# v2164_quad_VC_mixer_0402.net
KiCad netlist of a schematic drawn in EAGLE
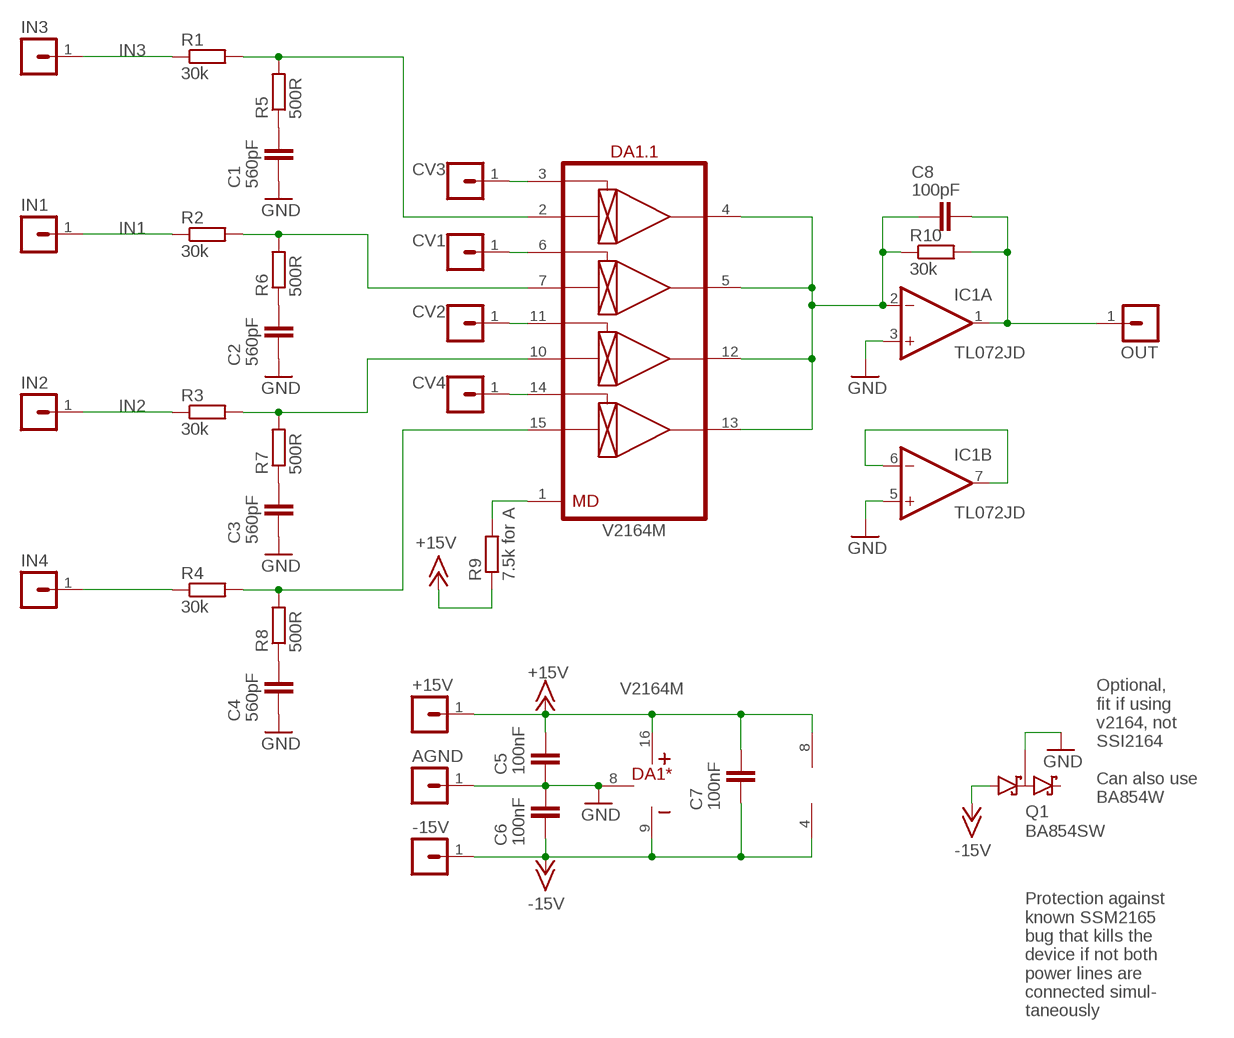
[diagram p0: schematic, sheet 1]

(export (version "E")
  (design (tool "Eeschema 10.0.6"))
  (components
    (comp (ref "+15V")
      (value "MA01-1JN")
      (footprint "eagle-import:MA01N-1J")
      (libsource (lib "eagle-import") (part "MA01-1JN"))
    )
    (comp (ref "-15V")
      (value "MA01-1JN")
      (footprint "eagle-import:MA01N-1J")
      (libsource (lib "eagle-import") (part "MA01-1JN"))
    )
    (comp (ref "AGND")
      (value "MA01-1JN")
      (footprint "eagle-import:MA01N-1J")
      (libsource (lib "eagle-import") (part "MA01-1JN"))
    )
    (comp (ref "C1")
      (value "560pF")
      (footprint "eagle-import:C0603")
      (libsource (lib "eagle-import") (part "C-EUC0603"))
    )
    (comp (ref "C2")
      (value "560pF")
      (footprint "eagle-import:C0603")
      (libsource (lib "eagle-import") (part "C-EUC0603"))
    )
    (comp (ref "C3")
      (value "560pF")
      (footprint "eagle-import:C0603")
      (libsource (lib "eagle-import") (part "C-EUC0603"))
    )
    (comp (ref "C4")
      (value "560pF")
      (footprint "eagle-import:C0603")
      (libsource (lib "eagle-import") (part "C-EUC0603"))
    )
    (comp (ref "C5")
      (value "100nF")
      (footprint "eagle-import:C0402")
      (libsource (lib "eagle-import") (part "C-EUC0402"))
    )
    (comp (ref "C6")
      (value "100nF")
      (footprint "eagle-import:C0402")
      (libsource (lib "eagle-import") (part "C-EUC0402"))
    )
    (comp (ref "C7")
      (value "100nF")
      (footprint "eagle-import:C0402")
      (libsource (lib "eagle-import") (part "C-EUC0402"))
    )
    (comp (ref "C8")
      (value "100pF")
      (footprint "eagle-import:C0402")
      (libsource (lib "eagle-import") (part "C-EUC0402"))
    )
    (comp (ref "CV1")
      (value "MA01-1JN")
      (footprint "eagle-import:MA01N-1J")
      (libsource (lib "eagle-import") (part "MA01-1JN"))
    )
    (comp (ref "CV2")
      (value "MA01-1JN")
      (footprint "eagle-import:MA01N-1J")
      (libsource (lib "eagle-import") (part "MA01-1JN"))
    )
    (comp (ref "CV3")
      (value "MA01-1JN")
      (footprint "eagle-import:MA01N-1J")
      (libsource (lib "eagle-import") (part "MA01-1JN"))
    )
    (comp (ref "CV4")
      (value "MA01-1JN")
      (footprint "eagle-import:MA01N-1J")
      (libsource (lib "eagle-import") (part "MA01-1JN"))
    )
    (comp (ref "DA1")
      (value "V2164M")
      (footprint "eagle-import:SO-16")
      (libsource (lib "eagle-import") (part "V2164M"))
    )
    (comp (ref "IC1")
      (value "TL072JD")
      (footprint "eagle-import:SO08J")
      (libsource (lib "eagle-import") (part "TL072JD"))
    )
    (comp (ref "IN1")
      (value "MA01-1JN")
      (footprint "eagle-import:MA01N-1J")
      (libsource (lib "eagle-import") (part "MA01-1JN"))
    )
    (comp (ref "IN2")
      (value "MA01-1JN")
      (footprint "eagle-import:MA01N-1J")
      (libsource (lib "eagle-import") (part "MA01-1JN"))
    )
    (comp (ref "IN3")
      (value "MA01-1JN")
      (footprint "eagle-import:MA01N-1J")
      (libsource (lib "eagle-import") (part "MA01-1JN"))
    )
    (comp (ref "IN4")
      (value "MA01-1JN")
      (footprint "eagle-import:MA01N-1J")
      (libsource (lib "eagle-import") (part "MA01-1JN"))
    )
    (comp (ref "OUT")
      (value "MA01-1JN")
      (footprint "eagle-import:MA01N-1J")
      (libsource (lib "eagle-import") (part "MA01-1JN"))
    )
    (comp (ref "Q1")
      (value "BA854SW")
      (footprint "eagle-import:SOT23-3J")
      (libsource (lib "eagle-import") (part "BA854SW"))
    )
    (comp (ref "R1")
      (value "30k")
      (footprint "eagle-import:R0402")
      (libsource (lib "eagle-import") (part "R-EU_R0402"))
    )
    (comp (ref "R2")
      (value "30k")
      (footprint "eagle-import:R0402")
      (libsource (lib "eagle-import") (part "R-EU_R0402"))
    )
    (comp (ref "R3")
      (value "30k")
      (footprint "eagle-import:R0402")
      (libsource (lib "eagle-import") (part "R-EU_R0402"))
    )
    (comp (ref "R4")
      (value "30k")
      (footprint "eagle-import:R0402")
      (libsource (lib "eagle-import") (part "R-EU_R0402"))
    )
    (comp (ref "R5")
      (value "500R")
      (footprint "eagle-import:R0402")
      (libsource (lib "eagle-import") (part "R-EU_R0402"))
    )
    (comp (ref "R6")
      (value "500R")
      (footprint "eagle-import:R0402")
      (libsource (lib "eagle-import") (part "R-EU_R0402"))
    )
    (comp (ref "R7")
      (value "500R")
      (footprint "eagle-import:R0402")
      (libsource (lib "eagle-import") (part "R-EU_R0402"))
    )
    (comp (ref "R8")
      (value "500R")
      (footprint "eagle-import:R0402")
      (libsource (lib "eagle-import") (part "R-EU_R0402"))
    )
    (comp (ref "R9")
      (value "7.5k for A")
      (footprint "eagle-import:R0402")
      (libsource (lib "eagle-import") (part "R-EU_R0402"))
    )
    (comp (ref "R10")
      (value "30k")
      (footprint "eagle-import:R0402")
      (libsource (lib "eagle-import") (part "R-EU_R0402"))
    )
  )
  (nets
    (net (code "1") (name "+15V") (class "Default")
      (node (ref "+15V") (pin "1") (pinfunction "1_1") (pintype "passive"))
      (node (ref "C5") (pin "2") (pinfunction "2_2") (pintype "passive"))
      (node (ref "C7") (pin "2") (pinfunction "2_2") (pintype "passive"))
      (node (ref "DA1") (pin "16") (pinfunction "V+_16") (pintype "power_in"))
      (node (ref "IC1") (pin "8") (pinfunction "V+_8") (pintype "power_in"))
      (node (ref "R9") (pin "1") (pinfunction "1_1") (pintype "passive"))
    )
    (net (code "2") (name "-15V") (class "Default")
      (node (ref "-15V") (pin "1") (pinfunction "1_1") (pintype "passive"))
      (node (ref "C6") (pin "1") (pinfunction "1_1") (pintype "passive"))
      (node (ref "C7") (pin "1") (pinfunction "1_1") (pintype "passive"))
      (node (ref "DA1") (pin "9") (pinfunction "V-_9") (pintype "power_in"))
      (node (ref "IC1") (pin "4") (pinfunction "V-_4") (pintype "power_in"))
      (node (ref "Q1") (pin "1") (pinfunction "A1_1") (pintype "passive"))
    )
    (net (code "3") (name "/IN1") (class "Default")
      (node (ref "IN1") (pin "1") (pinfunction "1_1") (pintype "passive"))
      (node (ref "R2") (pin "1") (pinfunction "1_1") (pintype "passive"))
    )
    (net (code "4") (name "/IN2") (class "Default")
      (node (ref "IN2") (pin "1") (pinfunction "1_1") (pintype "passive"))
      (node (ref "R3") (pin "1") (pinfunction "1_1") (pintype "passive"))
    )
    (net (code "5") (name "/IN3") (class "Default")
      (node (ref "IN3") (pin "1") (pinfunction "1_1") (pintype "passive"))
      (node (ref "R1") (pin "1") (pinfunction "1_1") (pintype "passive"))
    )
    (net (code "6") (name "GND") (class "Default")
      (node (ref "AGND") (pin "1") (pinfunction "1_1") (pintype "passive"))
      (node (ref "C1") (pin "1") (pinfunction "1_1") (pintype "passive"))
      (node (ref "C2") (pin "1") (pinfunction "1_1") (pintype "passive"))
      (node (ref "C3") (pin "1") (pinfunction "1_1") (pintype "passive"))
      (node (ref "C4") (pin "1") (pinfunction "1_1") (pintype "passive"))
      (node (ref "C5") (pin "1") (pinfunction "1_1") (pintype "passive"))
      (node (ref "C6") (pin "2") (pinfunction "2_2") (pintype "passive"))
      (node (ref "DA1") (pin "8") (pinfunction "GND_8") (pintype "power_in"))
      (node (ref "IC1") (pin "3") (pinfunction "+IN_3") (pintype "input"))
      (node (ref "IC1") (pin "5") (pinfunction "+IN_5") (pintype "input"))
      (node (ref "Q1") (pin "3") (pinfunction "K1A2_3") (pintype "passive"))
    )
    (net (code "7") (name "Net-(C1-Pad2)") (class "Default")
      (node (ref "C1") (pin "2") (pinfunction "2_2") (pintype "passive"))
      (node (ref "R5") (pin "1") (pinfunction "1_1") (pintype "passive"))
    )
    (net (code "8") (name "Net-(C2-Pad2)") (class "Default")
      (node (ref "C2") (pin "2") (pinfunction "2_2") (pintype "passive"))
      (node (ref "R6") (pin "1") (pinfunction "1_1") (pintype "passive"))
    )
    (net (code "9") (name "Net-(C3-Pad2)") (class "Default")
      (node (ref "C3") (pin "2") (pinfunction "2_2") (pintype "passive"))
      (node (ref "R7") (pin "1") (pinfunction "1_1") (pintype "passive"))
    )
    (net (code "10") (name "Net-(C4-Pad2)") (class "Default")
      (node (ref "C4") (pin "2") (pinfunction "2_2") (pintype "passive"))
      (node (ref "R8") (pin "1") (pinfunction "1_1") (pintype "passive"))
    )
    (net (code "11") (name "Net-(DA1B-CV1)") (class "Default")
      (node (ref "CV3") (pin "1") (pinfunction "1_1") (pintype "passive"))
      (node (ref "DA1") (pin "3") (pinfunction "CV1_3") (pintype "input"))
    )
    (net (code "12") (name "Net-(DA1B-CV2)") (class "Default")
      (node (ref "CV1") (pin "1") (pinfunction "1_1") (pintype "passive"))
      (node (ref "DA1") (pin "6") (pinfunction "CV2_6") (pintype "input"))
    )
    (net (code "13") (name "Net-(DA1B-CV3)") (class "Default")
      (node (ref "CV2") (pin "1") (pinfunction "1_1") (pintype "passive"))
      (node (ref "DA1") (pin "11") (pinfunction "CV3_11") (pintype "input"))
    )
    (net (code "14") (name "Net-(DA1B-CV4)") (class "Default")
      (node (ref "CV4") (pin "1") (pinfunction "1_1") (pintype "passive"))
      (node (ref "DA1") (pin "14") (pinfunction "CV4_14") (pintype "input"))
    )
    (net (code "15") (name "Net-(DA1B-IN1)") (class "Default")
      (node (ref "DA1") (pin "2") (pinfunction "IN1_2") (pintype "input"))
      (node (ref "R1") (pin "2") (pinfunction "2_2") (pintype "passive"))
      (node (ref "R5") (pin "2") (pinfunction "2_2") (pintype "passive"))
    )
    (net (code "16") (name "Net-(DA1B-IN2)") (class "Default")
      (node (ref "DA1") (pin "7") (pinfunction "IN2_7") (pintype "input"))
      (node (ref "R2") (pin "2") (pinfunction "2_2") (pintype "passive"))
      (node (ref "R6") (pin "2") (pinfunction "2_2") (pintype "passive"))
    )
    (net (code "17") (name "Net-(DA1B-IN3)") (class "Default")
      (node (ref "DA1") (pin "10") (pinfunction "IN3_10") (pintype "input"))
      (node (ref "R3") (pin "2") (pinfunction "2_2") (pintype "passive"))
      (node (ref "R7") (pin "2") (pinfunction "2_2") (pintype "passive"))
    )
    (net (code "18") (name "Net-(DA1B-IN4)") (class "Default")
      (node (ref "DA1") (pin "15") (pinfunction "IN4_15") (pintype "input"))
      (node (ref "R4") (pin "2") (pinfunction "2_2") (pintype "passive"))
      (node (ref "R8") (pin "2") (pinfunction "2_2") (pintype "passive"))
    )
    (net (code "19") (name "Net-(DA1B-MD)") (class "Default")
      (node (ref "DA1") (pin "1") (pinfunction "MD_1") (pintype "output"))
      (node (ref "R9") (pin "2") (pinfunction "2_2") (pintype "passive"))
    )
    (net (code "20") (name "Net-(DA1B-OUT1)") (class "Default")
      (node (ref "C8") (pin "1") (pinfunction "1_1") (pintype "passive"))
      (node (ref "DA1") (pin "12") (pinfunction "OUT3_12") (pintype "output"))
      (node (ref "DA1") (pin "13") (pinfunction "OUT4_13") (pintype "output"))
      (node (ref "DA1") (pin "4") (pinfunction "OUT1_4") (pintype "output"))
      (node (ref "DA1") (pin "5") (pinfunction "OUT2_5") (pintype "output"))
      (node (ref "IC1") (pin "2") (pinfunction "-IN_2") (pintype "input"))
      (node (ref "R10") (pin "1") (pinfunction "1_1") (pintype "passive"))
    )
    (net (code "21") (name "Net-(IC1A-OUT)") (class "Default")
      (node (ref "C8") (pin "2") (pinfunction "2_2") (pintype "passive"))
      (node (ref "IC1") (pin "1") (pinfunction "OUT_1") (pintype "output"))
      (node (ref "OUT") (pin "1") (pinfunction "1_1") (pintype "passive"))
      (node (ref "R10") (pin "2") (pinfunction "2_2") (pintype "passive"))
    )
    (net (code "22") (name "Net-(IC1B--IN)") (class "Default")
      (node (ref "IC1") (pin "6") (pinfunction "-IN_6") (pintype "input"))
      (node (ref "IC1") (pin "7") (pinfunction "OUT_7") (pintype "output"))
    )
    (net (code "23") (name "Net-(IN4-Pad1)") (class "Default")
      (node (ref "IN4") (pin "1") (pinfunction "1_1") (pintype "passive"))
      (node (ref "R4") (pin "1") (pinfunction "1_1") (pintype "passive"))
    )
    (net (code "24") (name "unconnected-(Q1-K2-Pad2)") (class "Default")
      (node (ref "Q1") (pin "2") (pinfunction "K2_2") (pintype "passive"))
    )
  )
)
